# led-mosfet.net
KiCad netlist of a schematic drawn in EAGLE
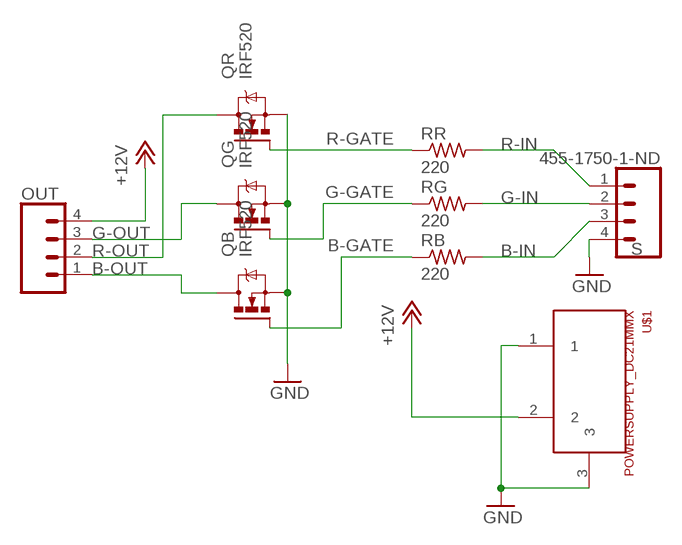
[diagram p0: schematic, sheet 1]

(export (version "E")
  (design (tool "Eeschema 10.0.6"))
  (components
    (comp (ref "OUT")
      (value "CONN_04")
      (footprint "eagle-import:1X04")
      (libsource (lib "eagle-import") (part "CONN_04"))
    )
    (comp (ref "QB")
      (value "IRF520")
      (footprint "eagle-import:TO220BV")
      (libsource (lib "eagle-import") (part "IRF520"))
    )
    (comp (ref "QG")
      (value "IRF520")
      (footprint "eagle-import:TO220BV")
      (libsource (lib "eagle-import") (part "IRF520"))
    )
    (comp (ref "QR")
      (value "IRF520")
      (footprint "eagle-import:TO220BV")
      (libsource (lib "eagle-import") (part "IRF520"))
    )
    (comp (ref "RB")
      (value "220")
      (footprint "eagle-import:R0805")
      (libsource (lib "eagle-import") (part "R-US_R0805"))
    )
    (comp (ref "RG")
      (value "220")
      (footprint "eagle-import:R0805")
      (libsource (lib "eagle-import") (part "R-US_R0805"))
    )
    (comp (ref "RR")
      (value "220")
      (footprint "eagle-import:R0805")
      (libsource (lib "eagle-import") (part "R-US_R0805"))
    )
    (comp (ref "S")
      (value "455-1750-1-ND")
      (footprint "eagle-import:1X04")
      (libsource (lib "eagle-import") (part "CONN_04"))
    )
    (comp (ref "U$1")
      (value "POWERSUPPLY_DC21MMX")
      (footprint "eagle-import:POWERSUPPLY_DC-21MM")
      (libsource (lib "eagle-import") (part "POWERSUPPLY_DC21MMX"))
    )
  )
  (nets
    (net (code "1") (name "+12V") (class "Default")
      (node (ref "OUT") (pin "4") (pinfunction "4_4") (pintype "passive"))
      (node (ref "U$1") (pin "2") (pinfunction "2_2") (pintype "power_in"))
    )
    (net (code "2") (name "/B-GATE") (class "Default")
      (node (ref "QB") (pin "G") (pinfunction "G_G") (pintype "passive"))
      (node (ref "RB") (pin "1") (pinfunction "1_1") (pintype "passive"))
    )
    (net (code "3") (name "/B-IN") (class "Default")
      (node (ref "RB") (pin "2") (pinfunction "2_2") (pintype "passive"))
      (node (ref "S") (pin "3") (pinfunction "3_3") (pintype "passive"))
    )
    (net (code "4") (name "/B-OUT") (class "Default")
      (node (ref "OUT") (pin "1") (pinfunction "1_1") (pintype "passive"))
      (node (ref "QB") (pin "D") (pinfunction "D_D") (pintype "passive"))
    )
    (net (code "5") (name "/G-GATE") (class "Default")
      (node (ref "QG") (pin "G") (pinfunction "G_G") (pintype "passive"))
      (node (ref "RG") (pin "1") (pinfunction "1_1") (pintype "passive"))
    )
    (net (code "6") (name "/G-IN") (class "Default")
      (node (ref "RG") (pin "2") (pinfunction "2_2") (pintype "passive"))
      (node (ref "S") (pin "2") (pinfunction "2_2") (pintype "passive"))
    )
    (net (code "7") (name "/G-OUT") (class "Default")
      (node (ref "OUT") (pin "3") (pinfunction "3_3") (pintype "passive"))
      (node (ref "QG") (pin "D") (pinfunction "D_D") (pintype "passive"))
    )
    (net (code "8") (name "/R-GATE") (class "Default")
      (node (ref "QR") (pin "G") (pinfunction "G_G") (pintype "passive"))
      (node (ref "RR") (pin "1") (pinfunction "1_1") (pintype "passive"))
    )
    (net (code "9") (name "/R-IN") (class "Default")
      (node (ref "RR") (pin "2") (pinfunction "2_2") (pintype "passive"))
      (node (ref "S") (pin "1") (pinfunction "1_1") (pintype "passive"))
    )
    (net (code "10") (name "/R-OUT") (class "Default")
      (node (ref "OUT") (pin "2") (pinfunction "2_2") (pintype "passive"))
      (node (ref "QR") (pin "D") (pinfunction "D_D") (pintype "passive"))
    )
    (net (code "11") (name "GND") (class "Default")
      (node (ref "QB") (pin "S") (pinfunction "S_S") (pintype "passive"))
      (node (ref "QG") (pin "S") (pinfunction "S_S") (pintype "passive"))
      (node (ref "QR") (pin "S") (pinfunction "S_S") (pintype "passive"))
      (node (ref "S") (pin "4") (pinfunction "4_4") (pintype "passive"))
      (node (ref "U$1") (pin "1") (pinfunction "1_1") (pintype "power_in"))
      (node (ref "U$1") (pin "3") (pinfunction "3_3") (pintype "power_in"))
    )
  )
)
